# power.net
KiCad netlist of a schematic drawn in Altium Designer
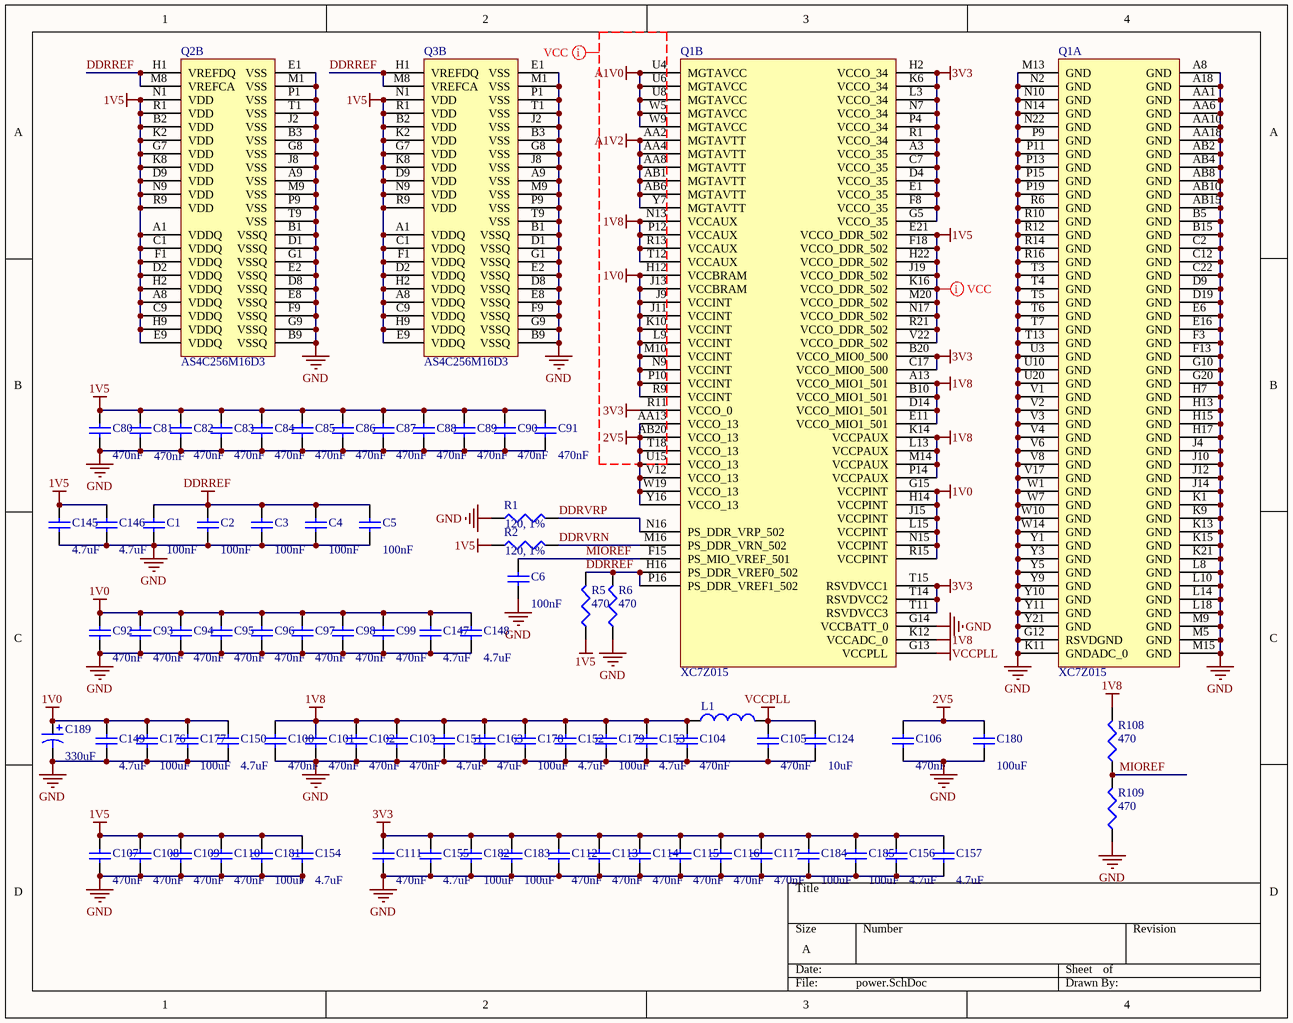
[diagram p0: power.SchDoc]

(export (version "E")
  (design (tool "Eeschema 10.0.6"))
  (components
    (comp (ref "C1")
      (value "100nF")
      (footprint "CAPC1005X06L")
      (description "Capacitor")
      (fields (field (name "Comment") "Cap") (field (name "PUBLISHER") "Altium Limited"))
      (libsource (lib "Miscellaneous Devices") (part "Cap"))
    )
    (comp (ref "C2")
      (value "100nF")
      (footprint "CAPC1005X06L")
      (description "Capacitor")
      (fields (field (name "Comment") "Cap") (field (name "PUBLISHER") "Altium Limited"))
      (libsource (lib "Miscellaneous Devices") (part "Cap"))
    )
    (comp (ref "C3")
      (value "100nF")
      (footprint "CAPC1005X06L")
      (description "Capacitor")
      (fields (field (name "Comment") "Cap") (field (name "PUBLISHER") "Altium Limited"))
      (libsource (lib "Miscellaneous Devices") (part "Cap"))
    )
    (comp (ref "C4")
      (value "100nF")
      (footprint "CAPC1005X06L")
      (description "Capacitor")
      (fields (field (name "Comment") "Cap") (field (name "PUBLISHER") "Altium Limited"))
      (libsource (lib "Miscellaneous Devices") (part "Cap"))
    )
    (comp (ref "C5")
      (value "100nF")
      (footprint "CAPC1005X06L")
      (description "Capacitor")
      (fields (field (name "Comment") "Cap") (field (name "PUBLISHER") "Altium Limited"))
      (libsource (lib "Miscellaneous Devices") (part "Cap"))
    )
    (comp (ref "C6")
      (value "100nF")
      (footprint "CAPC1005X06L")
      (description "Capacitor")
      (fields (field (name "Comment") "Cap") (field (name "PUBLISHER") "Altium Limited"))
      (libsource (lib "Miscellaneous Devices") (part "Cap"))
    )
    (comp (ref "C80")
      (value "470nF")
      (footprint "CAPC1005X06L")
      (description "Capacitor")
      (fields (field (name "Comment") "JMK105BJ474KV-F") (field (name "PUBLISHER") "Altium Limited"))
      (libsource (lib "Miscellaneous Devices") (part "Cap"))
    )
    (comp (ref "C81")
      (value "470nF")
      (footprint "CAPC1005X06L")
      (description "Capacitor")
      (fields (field (name "Comment") "JMK105BJ474KV-F") (field (name "PUBLISHER") "Altium Limited"))
      (libsource (lib "Miscellaneous Devices") (part "Cap"))
    )
    (comp (ref "C82")
      (value "470nF")
      (footprint "CAPC1005X06L")
      (description "Capacitor")
      (fields (field (name "Comment") "JMK105BJ474KV-F") (field (name "PUBLISHER") "Altium Limited"))
      (libsource (lib "Miscellaneous Devices") (part "Cap"))
    )
    (comp (ref "C83")
      (value "470nF")
      (footprint "CAPC1005X06L")
      (description "Capacitor")
      (fields (field (name "Comment") "JMK105BJ474KV-F") (field (name "PUBLISHER") "Altium Limited"))
      (libsource (lib "Miscellaneous Devices") (part "Cap"))
    )
    (comp (ref "C84")
      (value "470nF")
      (footprint "CAPC1005X06L")
      (description "Capacitor")
      (fields (field (name "Comment") "JMK105BJ474KV-F") (field (name "PUBLISHER") "Altium Limited"))
      (libsource (lib "Miscellaneous Devices") (part "Cap"))
    )
    (comp (ref "C85")
      (value "470nF")
      (footprint "CAPC1005X06L")
      (description "Capacitor")
      (fields (field (name "Comment") "JMK105BJ474KV-F") (field (name "PUBLISHER") "Altium Limited"))
      (libsource (lib "Miscellaneous Devices") (part "Cap"))
    )
    (comp (ref "C86")
      (value "470nF")
      (footprint "CAPC1005X06L")
      (description "Capacitor")
      (fields (field (name "Comment") "JMK105BJ474KV-F") (field (name "PUBLISHER") "Altium Limited"))
      (libsource (lib "Miscellaneous Devices") (part "Cap"))
    )
    (comp (ref "C87")
      (value "470nF")
      (footprint "CAPC1005X06L")
      (description "Capacitor")
      (fields (field (name "Comment") "JMK105BJ474KV-F") (field (name "PUBLISHER") "Altium Limited"))
      (libsource (lib "Miscellaneous Devices") (part "Cap"))
    )
    (comp (ref "C88")
      (value "470nF")
      (footprint "CAPC1005X06L")
      (description "Capacitor")
      (fields (field (name "Comment") "JMK105BJ474KV-F") (field (name "PUBLISHER") "Altium Limited"))
      (libsource (lib "Miscellaneous Devices") (part "Cap"))
    )
    (comp (ref "C89")
      (value "470nF")
      (footprint "CAPC1005X06L")
      (description "Capacitor")
      (fields (field (name "Comment") "JMK105BJ474KV-F") (field (name "PUBLISHER") "Altium Limited"))
      (libsource (lib "Miscellaneous Devices") (part "Cap"))
    )
    (comp (ref "C90")
      (value "470nF")
      (footprint "CAPC1005X06L")
      (description "Capacitor")
      (fields (field (name "Comment") "JMK105BJ474KV-F") (field (name "PUBLISHER") "Altium Limited"))
      (libsource (lib "Miscellaneous Devices") (part "Cap"))
    )
    (comp (ref "C91")
      (value "470nF")
      (footprint "CAPC1005X06L")
      (description "Capacitor")
      (fields (field (name "Comment") "JMK105BJ474KV-F") (field (name "PUBLISHER") "Altium Limited"))
      (libsource (lib "Miscellaneous Devices") (part "Cap"))
    )
    (comp (ref "C92")
      (value "470nF")
      (footprint "CAPC1005X06L")
      (description "Capacitor")
      (fields (field (name "Comment") "JMK105BJ474KV-F") (field (name "PUBLISHER") "Altium Limited"))
      (libsource (lib "Miscellaneous Devices") (part "Cap"))
    )
    (comp (ref "C93")
      (value "470nF")
      (footprint "CAPC1005X06L")
      (description "Capacitor")
      (fields (field (name "Comment") "JMK105BJ474KV-F") (field (name "PUBLISHER") "Altium Limited"))
      (libsource (lib "Miscellaneous Devices") (part "Cap"))
    )
    (comp (ref "C94")
      (value "470nF")
      (footprint "CAPC1005X06L")
      (description "Capacitor")
      (fields (field (name "Comment") "JMK105BJ474KV-F") (field (name "PUBLISHER") "Altium Limited"))
      (libsource (lib "Miscellaneous Devices") (part "Cap"))
    )
    (comp (ref "C95")
      (value "470nF")
      (footprint "CAPC1005X06L")
      (description "Capacitor")
      (fields (field (name "Comment") "JMK105BJ474KV-F") (field (name "PUBLISHER") "Altium Limited"))
      (libsource (lib "Miscellaneous Devices") (part "Cap"))
    )
    (comp (ref "C96")
      (value "470nF")
      (footprint "CAPC1005X06L")
      (description "Capacitor")
      (fields (field (name "Comment") "JMK105BJ474KV-F") (field (name "PUBLISHER") "Altium Limited"))
      (libsource (lib "Miscellaneous Devices") (part "Cap"))
    )
    (comp (ref "C97")
      (value "470nF")
      (footprint "CAPC1005X06L")
      (description "Capacitor")
      (fields (field (name "Comment") "JMK105BJ474KV-F") (field (name "PUBLISHER") "Altium Limited"))
      (libsource (lib "Miscellaneous Devices") (part "Cap"))
    )
    (comp (ref "C98")
      (value "470nF")
      (footprint "CAPC1005X06L")
      (description "Capacitor")
      (fields (field (name "Comment") "JMK105BJ474KV-F") (field (name "PUBLISHER") "Altium Limited"))
      (libsource (lib "Miscellaneous Devices") (part "Cap"))
    )
    (comp (ref "C99")
      (value "470nF")
      (footprint "CAPC1005X06L")
      (description "Capacitor")
      (fields (field (name "Comment") "JMK105BJ474KV-F") (field (name "PUBLISHER") "Altium Limited"))
      (libsource (lib "Miscellaneous Devices") (part "Cap"))
    )
    (comp (ref "C100")
      (value "470nF")
      (footprint "CAPC1005X06L")
      (description "Capacitor")
      (fields (field (name "Comment") "JMK105BJ474KV-F") (field (name "PUBLISHER") "Altium Limited"))
      (libsource (lib "Miscellaneous Devices") (part "Cap"))
    )
    (comp (ref "C101")
      (value "470nF")
      (footprint "CAPC1005X06L")
      (description "Capacitor")
      (fields (field (name "Comment") "JMK105BJ474KV-F") (field (name "PUBLISHER") "Altium Limited"))
      (libsource (lib "Miscellaneous Devices") (part "Cap"))
    )
    (comp (ref "C102")
      (value "470nF")
      (footprint "CAPC1005X06L")
      (description "Capacitor")
      (fields (field (name "Comment") "JMK105BJ474KV-F") (field (name "PUBLISHER") "Altium Limited"))
      (libsource (lib "Miscellaneous Devices") (part "Cap"))
    )
    (comp (ref "C103")
      (value "470nF")
      (footprint "CAPC1005X06L")
      (description "Capacitor")
      (fields (field (name "Comment") "JMK105BJ474KV-F") (field (name "PUBLISHER") "Altium Limited"))
      (libsource (lib "Miscellaneous Devices") (part "Cap"))
    )
    (comp (ref "C104")
      (value "470nF")
      (footprint "CAPC1005X06L")
      (description "Capacitor")
      (fields (field (name "Comment") "JMK105BJ474KV-F") (field (name "PUBLISHER") "Altium Limited"))
      (libsource (lib "Miscellaneous Devices") (part "Cap"))
    )
    (comp (ref "C105")
      (value "470nF")
      (footprint "CAPC1005X06L")
      (description "Capacitor")
      (fields (field (name "Comment") "JMK105BJ474KV-F") (field (name "PUBLISHER") "Altium Limited"))
      (libsource (lib "Miscellaneous Devices") (part "Cap"))
    )
    (comp (ref "C106")
      (value "470nF")
      (footprint "CAPC1005X06L")
      (description "Capacitor")
      (fields (field (name "Comment") "JMK105BJ474KV-F") (field (name "PUBLISHER") "Altium Limited"))
      (libsource (lib "Miscellaneous Devices") (part "Cap"))
    )
    (comp (ref "C107")
      (value "470nF")
      (footprint "CAPC1005X06L")
      (description "Capacitor")
      (fields (field (name "Comment") "JMK105BJ474KV-F") (field (name "PUBLISHER") "Altium Limited"))
      (libsource (lib "Miscellaneous Devices") (part "Cap"))
    )
    (comp (ref "C108")
      (value "470nF")
      (footprint "CAPC1005X06L")
      (description "Capacitor")
      (fields (field (name "Comment") "JMK105BJ474KV-F") (field (name "PUBLISHER") "Altium Limited"))
      (libsource (lib "Miscellaneous Devices") (part "Cap"))
    )
    (comp (ref "C109")
      (value "470nF")
      (footprint "CAPC1005X06L")
      (description "Capacitor")
      (fields (field (name "Comment") "JMK105BJ474KV-F") (field (name "PUBLISHER") "Altium Limited"))
      (libsource (lib "Miscellaneous Devices") (part "Cap"))
    )
    (comp (ref "C110")
      (value "470nF")
      (footprint "CAPC1005X06L")
      (description "Capacitor")
      (fields (field (name "Comment") "JMK105BJ474KV-F") (field (name "PUBLISHER") "Altium Limited"))
      (libsource (lib "Miscellaneous Devices") (part "Cap"))
    )
    (comp (ref "C111")
      (value "470nF")
      (footprint "CAPC1005X06L")
      (description "Capacitor")
      (fields (field (name "Comment") "JMK105BJ474KV-F") (field (name "PUBLISHER") "Altium Limited"))
      (libsource (lib "Miscellaneous Devices") (part "Cap"))
    )
    (comp (ref "C112")
      (value "470nF")
      (footprint "CAPC1005X06L")
      (description "Capacitor")
      (fields (field (name "Comment") "JMK105BJ474KV-F") (field (name "PUBLISHER") "Altium Limited"))
      (libsource (lib "Miscellaneous Devices") (part "Cap"))
    )
    (comp (ref "C113")
      (value "470nF")
      (footprint "CAPC1005X06L")
      (description "Capacitor")
      (fields (field (name "Comment") "JMK105BJ474KV-F") (field (name "PUBLISHER") "Altium Limited"))
      (libsource (lib "Miscellaneous Devices") (part "Cap"))
    )
    (comp (ref "C114")
      (value "470nF")
      (footprint "CAPC1005X06L")
      (description "Capacitor")
      (fields (field (name "Comment") "JMK105BJ474KV-F") (field (name "PUBLISHER") "Altium Limited"))
      (libsource (lib "Miscellaneous Devices") (part "Cap"))
    )
    (comp (ref "C115")
      (value "470nF")
      (footprint "CAPC1005X06L")
      (description "Capacitor")
      (fields (field (name "Comment") "JMK105BJ474KV-F") (field (name "PUBLISHER") "Altium Limited"))
      (libsource (lib "Miscellaneous Devices") (part "Cap"))
    )
    (comp (ref "C116")
      (value "470nF")
      (footprint "CAPC1005X06L")
      (description "Capacitor")
      (fields (field (name "Comment") "JMK105BJ474KV-F") (field (name "PUBLISHER") "Altium Limited"))
      (libsource (lib "Miscellaneous Devices") (part "Cap"))
    )
    (comp (ref "C117")
      (value "470nF")
      (footprint "CAPC1005X06L")
      (description "Capacitor")
      (fields (field (name "Comment") "JMK105BJ474KV-F") (field (name "PUBLISHER") "Altium Limited"))
      (libsource (lib "Miscellaneous Devices") (part "Cap"))
    )
    (comp (ref "C124")
      (value "10uF")
      (footprint "CAPC1608X90N")
      (description "Capacitor")
      (fields (field (name "Comment") "GRM188R60G106ME47") (field (name "PUBLISHER") "Altium Limited"))
      (libsource (lib "Miscellaneous Devices") (part "Cap"))
    )
    (comp (ref "C145")
      (value "4.7uF")
      (footprint "CAPC1608X90N")
      (description "Capacitor")
      (fields (field (name "Comment") "GRM188R60J475ME19D") (field (name "PUBLISHER") "Altium Limited"))
      (libsource (lib "Miscellaneous Devices") (part "Cap"))
    )
    (comp (ref "C146")
      (value "4.7uF")
      (footprint "CAPC1608X90N")
      (description "Capacitor")
      (fields (field (name "Comment") "GRM188R60J475ME19D") (field (name "PUBLISHER") "Altium Limited"))
      (libsource (lib "Miscellaneous Devices") (part "Cap"))
    )
    (comp (ref "C147")
      (value "4.7uF")
      (footprint "CAPC1608X90N")
      (description "Capacitor")
      (fields (field (name "Comment") "GRM188R60J475ME19D") (field (name "PUBLISHER") "Altium Limited"))
      (libsource (lib "Miscellaneous Devices") (part "Cap"))
    )
    (comp (ref "C148")
      (value "4.7uF")
      (footprint "CAPC1608X90N")
      (description "Capacitor")
      (fields (field (name "Comment") "GRM188R60J475ME19D") (field (name "PUBLISHER") "Altium Limited"))
      (libsource (lib "Miscellaneous Devices") (part "Cap"))
    )
    (comp (ref "C149")
      (value "4.7uF")
      (footprint "CAPC1608X90N")
      (description "Capacitor")
      (fields (field (name "Comment") "GRM188R60J475ME19D") (field (name "PUBLISHER") "Altium Limited"))
      (libsource (lib "Miscellaneous Devices") (part "Cap"))
    )
    (comp (ref "C150")
      (value "4.7uF")
      (footprint "CAPC1608X90N")
      (description "Capacitor")
      (fields (field (name "Comment") "GRM188R60J475ME19D") (field (name "PUBLISHER") "Altium Limited"))
      (libsource (lib "Miscellaneous Devices") (part "Cap"))
    )
    (comp (ref "C151")
      (value "4.7uF")
      (footprint "CAPC1608X90N")
      (description "Capacitor")
      (fields (field (name "Comment") "GRM188R60J475ME19D") (field (name "PUBLISHER") "Altium Limited"))
      (libsource (lib "Miscellaneous Devices") (part "Cap"))
    )
    (comp (ref "C152")
      (value "4.7uF")
      (footprint "CAPC1608X90N")
      (description "Capacitor")
      (fields (field (name "Comment") "GRM188R60J475ME19D") (field (name "PUBLISHER") "Altium Limited"))
      (libsource (lib "Miscellaneous Devices") (part "Cap"))
    )
    (comp (ref "C153")
      (value "4.7uF")
      (footprint "CAPC1608X90N")
      (description "Capacitor")
      (fields (field (name "Comment") "GRM188R60J475ME19D") (field (name "PUBLISHER") "Altium Limited"))
      (libsource (lib "Miscellaneous Devices") (part "Cap"))
    )
    (comp (ref "C154")
      (value "4.7uF")
      (footprint "CAPC1608X90N")
      (description "Capacitor")
      (fields (field (name "Comment") "GRM188R60J475ME19D") (field (name "PUBLISHER") "Altium Limited"))
      (libsource (lib "Miscellaneous Devices") (part "Cap"))
    )
    (comp (ref "C155")
      (value "4.7uF")
      (footprint "CAPC1608X90N")
      (description "Capacitor")
      (fields (field (name "Comment") "GRM188R60J475ME19D") (field (name "PUBLISHER") "Altium Limited"))
      (libsource (lib "Miscellaneous Devices") (part "Cap"))
    )
    (comp (ref "C156")
      (value "4.7uF")
      (footprint "CAPC1608X90N")
      (description "Capacitor")
      (fields (field (name "Comment") "GRM188R60J475ME19D") (field (name "PUBLISHER") "Altium Limited"))
      (libsource (lib "Miscellaneous Devices") (part "Cap"))
    )
    (comp (ref "C157")
      (value "4.7uF")
      (footprint "CAPC1608X90N")
      (description "Capacitor")
      (fields (field (name "Comment") "GRM188R60J475ME19D") (field (name "PUBLISHER") "Altium Limited"))
      (libsource (lib "Miscellaneous Devices") (part "Cap"))
    )
    (comp (ref "C163")
      (value "47uF")
      (footprint "CAPC3225X220N")
      (description "Capacitor")
      (fields (field (name "Comment") "GRM31CR60J476ME19L") (field (name "PUBLISHER") "Altium Limited"))
      (libsource (lib "Miscellaneous Devices") (part "Cap"))
    )
    (comp (ref "C176")
      (value "100uF")
      (footprint "CAPC3225X220N")
      (description "Capacitor")
      (fields (field (name "Comment") "GRM31CR60J107ME39L") (field (name "PUBLISHER") "Altium Limited"))
      (libsource (lib "Miscellaneous Devices") (part "Cap"))
    )
    (comp (ref "C177")
      (value "100uF")
      (footprint "CAPC3225X220N")
      (description "Capacitor")
      (fields (field (name "Comment") "GRM31CR60J107ME39L") (field (name "PUBLISHER") "Altium Limited"))
      (libsource (lib "Miscellaneous Devices") (part "Cap"))
    )
    (comp (ref "C178")
      (value "100uF")
      (footprint "CAPC3225X220N")
      (description "Capacitor")
      (fields (field (name "Comment") "GRM31CR60J107ME39L") (field (name "PUBLISHER") "Altium Limited"))
      (libsource (lib "Miscellaneous Devices") (part "Cap"))
    )
    (comp (ref "C179")
      (value "100uF")
      (footprint "CAPC3225X220N")
      (description "Capacitor")
      (fields (field (name "Comment") "GRM31CR60J107ME39L") (field (name "PUBLISHER") "Altium Limited"))
      (libsource (lib "Miscellaneous Devices") (part "Cap"))
    )
    (comp (ref "C180")
      (value "100uF")
      (footprint "CAPC3225X220N")
      (description "Capacitor")
      (fields (field (name "Comment") "GRM31CR60J107ME39L") (field (name "PUBLISHER") "Altium Limited"))
      (libsource (lib "Miscellaneous Devices") (part "Cap"))
    )
    (comp (ref "C181")
      (value "100uF")
      (footprint "CAPC3225X220N")
      (description "Capacitor")
      (fields (field (name "Comment") "GRM31CR60J107ME39L") (field (name "PUBLISHER") "Altium Limited"))
      (libsource (lib "Miscellaneous Devices") (part "Cap"))
    )
    (comp (ref "C182")
      (value "100uF")
      (footprint "CAPC3225X220N")
      (description "Capacitor")
      (fields (field (name "Comment") "GRM31CR60J107ME39L") (field (name "PUBLISHER") "Altium Limited"))
      (libsource (lib "Miscellaneous Devices") (part "Cap"))
    )
    (comp (ref "C183")
      (value "100uF")
      (footprint "CAPC3225X220N")
      (description "Capacitor")
      (fields (field (name "Comment") "GRM31CR60J107ME39L") (field (name "PUBLISHER") "Altium Limited"))
      (libsource (lib "Miscellaneous Devices") (part "Cap"))
    )
    (comp (ref "C184")
      (value "100uF")
      (footprint "CAPC3225X220N")
      (description "Capacitor")
      (fields (field (name "Comment") "GRM31CR60J107ME39L") (field (name "PUBLISHER") "Altium Limited"))
      (libsource (lib "Miscellaneous Devices") (part "Cap"))
    )
    (comp (ref "C185")
      (value "100uF")
      (footprint "CAPC3225X220N")
      (description "Capacitor")
      (fields (field (name "Comment") "GRM31CR60J107ME39L") (field (name "PUBLISHER") "Altium Limited"))
      (libsource (lib "Miscellaneous Devices") (part "Cap"))
    )
    (comp (ref "C189")
      (value "330uF")
      (footprint "CAP-D/7343-31")
      (description "Polarized Capacitor (Radial)")
      (fields (field (name "Comment") "T520D337M006ATE018") (field (name "PUBLISHER") "Altium Limited"))
      (libsource (lib "Miscellaneous Devices") (part "Cap Pol1"))
    )
    (comp (ref "L1")
      (value "BLM18SG121TN1")
      (footprint "CAPC1608X90N")
      (description "Inductor")
      (fields (field (name "PUBLISHER") "Altium Limited"))
      (libsource (lib "Miscellaneous Devices") (part "Inductor"))
    )
    (comp (ref "Q1") (value "XC7Z015") (footprint "BGA484x22") (libsource (lib "schlib") (part "XC7Z015")))
    (comp (ref "Q2")
      (value "AS4C256M16D3")
      (footprint "DDR3")
      (libsource (lib "schlib") (part "AS4C256M16D3"))
    )
    (comp (ref "Q3")
      (value "AS4C256M16D3")
      (footprint "DDR3")
      (libsource (lib "schlib") (part "AS4C256M16D3"))
    )
    (comp (ref "R1")
      (value "120, 1%")
      (footprint "CAPC1005X06L")
      (description "Resistor")
      (fields (field (name "Comment") "RC1005F121CS") (field (name "PUBLISHER") "Altium Limited"))
      (libsource (lib "Miscellaneous Devices") (part "Res3"))
    )
    (comp (ref "R2")
      (value "120, 1%")
      (footprint "CAPC1005X06L")
      (description "Resistor")
      (fields (field (name "Comment") "RC1005F121CS") (field (name "PUBLISHER") "Altium Limited"))
      (libsource (lib "Miscellaneous Devices") (part "Res3"))
    )
    (comp (ref "R5")
      (value "470")
      (footprint "J1-0603")
      (description "Resistor")
      (fields (field (name "Comment") "RC1608F471CS") (field (name "PUBLISHER") "Altium Limited"))
      (libsource (lib "Miscellaneous Devices") (part "Res3"))
    )
    (comp (ref "R6")
      (value "470")
      (footprint "J1-0603")
      (description "Resistor")
      (fields (field (name "Comment") "RC1608F471CS") (field (name "PUBLISHER") "Altium Limited"))
      (libsource (lib "Miscellaneous Devices") (part "Res3"))
    )
    (comp (ref "R108")
      (value "470")
      (footprint "CAPC1005X06L")
      (description "Resistor")
      (fields (field (name "Comment") "RC1005F471CS") (field (name "PUBLISHER") "Altium Limited"))
      (libsource (lib "Miscellaneous Devices") (part "Res3"))
    )
    (comp (ref "R109")
      (value "470")
      (footprint "CAPC1005X06L")
      (description "Resistor")
      (fields (field (name "Comment") "RC1005F471CS") (field (name "PUBLISHER") "Altium Limited"))
      (libsource (lib "Miscellaneous Devices") (part "Res3"))
    )
  )
  (nets
    (net (code "1") (name "/DDRVRN") (class "Default")
      (node (ref "Q1") (pin "M16") (pinfunction "PS_DDR_VRN_502_M16") (pintype "passive"))
      (node (ref "R2") (pin "2") (pinfunction "2_2") (pintype "passive"))
    )
    (net (code "2") (name "/DDRVRP") (class "Default")
      (node (ref "Q1") (pin "N16") (pinfunction "PS_DDR_VRP_502_N16") (pintype "passive"))
      (node (ref "R1") (pin "2") (pinfunction "2_2") (pintype "passive"))
    )
    (net (code "3") (name "/MIOREF") (class "Default")
      (node (ref "C6") (pin "2") (pinfunction "2_2") (pintype "passive"))
      (node (ref "Q1") (pin "F15") (pinfunction "PS_MIO_VREF_501_F15") (pintype "passive"))
      (node (ref "R108") (pin "1") (pinfunction "1_1") (pintype "passive"))
      (node (ref "R109") (pin "2") (pinfunction "2_2") (pintype "passive"))
    )
    (net (code "4") (name "1V0") (class "Default")
      (node (ref "C147") (pin "2") (pinfunction "2_2") (pintype "passive"))
      (node (ref "C148") (pin "2") (pinfunction "2_2") (pintype "passive"))
      (node (ref "C149") (pin "2") (pinfunction "2_2") (pintype "passive"))
      (node (ref "C150") (pin "2") (pinfunction "2_2") (pintype "passive"))
      (node (ref "C176") (pin "2") (pinfunction "2_2") (pintype "passive"))
      (node (ref "C177") (pin "2") (pinfunction "2_2") (pintype "passive"))
      (node (ref "C189") (pin "1") (pinfunction "1_1") (pintype "passive"))
      (node (ref "C92") (pin "2") (pinfunction "2_2") (pintype "passive"))
      (node (ref "C93") (pin "2") (pinfunction "2_2") (pintype "passive"))
      (node (ref "C94") (pin "2") (pinfunction "2_2") (pintype "passive"))
      (node (ref "C95") (pin "2") (pinfunction "2_2") (pintype "passive"))
      (node (ref "C96") (pin "2") (pinfunction "2_2") (pintype "passive"))
      (node (ref "C97") (pin "2") (pinfunction "2_2") (pintype "passive"))
      (node (ref "C98") (pin "2") (pinfunction "2_2") (pintype "passive"))
      (node (ref "C99") (pin "2") (pinfunction "2_2") (pintype "passive"))
      (node (ref "Q1") (pin "G15") (pinfunction "VCCPINT_G15") (pintype "passive"))
      (node (ref "Q1") (pin "H12") (pinfunction "VCCBRAM_H12") (pintype "passive"))
      (node (ref "Q1") (pin "H14") (pinfunction "VCCPINT_H14") (pintype "passive"))
      (node (ref "Q1") (pin "J11") (pinfunction "VCCINT_J11") (pintype "passive"))
      (node (ref "Q1") (pin "J13") (pinfunction "VCCBRAM_J13") (pintype "passive"))
      (node (ref "Q1") (pin "J15") (pinfunction "VCCPINT_J15") (pintype "passive"))
      (node (ref "Q1") (pin "J9") (pinfunction "VCCINT_J9") (pintype "passive"))
      (node (ref "Q1") (pin "K10") (pinfunction "VCCINT_K10") (pintype "passive"))
      (node (ref "Q1") (pin "L15") (pinfunction "VCCPINT_L15") (pintype "passive"))
      (node (ref "Q1") (pin "L9") (pinfunction "VCCINT_L9") (pintype "passive"))
      (node (ref "Q1") (pin "M10") (pinfunction "VCCINT_M10") (pintype "passive"))
      (node (ref "Q1") (pin "N15") (pinfunction "VCCPINT_N15") (pintype "passive"))
      (node (ref "Q1") (pin "N9") (pinfunction "VCCINT_N9") (pintype "passive"))
      (node (ref "Q1") (pin "P10") (pinfunction "VCCINT_P10") (pintype "passive"))
      (node (ref "Q1") (pin "R15") (pinfunction "VCCPINT_R15") (pintype "passive"))
      (node (ref "Q1") (pin "R9") (pinfunction "VCCINT_R9") (pintype "passive"))
    )
    (net (code "5") (name "1V5") (class "Default")
      (node (ref "C107") (pin "2") (pinfunction "2_2") (pintype "passive"))
      (node (ref "C108") (pin "2") (pinfunction "2_2") (pintype "passive"))
      (node (ref "C109") (pin "2") (pinfunction "2_2") (pintype "passive"))
      (node (ref "C110") (pin "2") (pinfunction "2_2") (pintype "passive"))
      (node (ref "C145") (pin "2") (pinfunction "2_2") (pintype "passive"))
      (node (ref "C146") (pin "2") (pinfunction "2_2") (pintype "passive"))
      (node (ref "C154") (pin "2") (pinfunction "2_2") (pintype "passive"))
      (node (ref "C181") (pin "2") (pinfunction "2_2") (pintype "passive"))
      (node (ref "C80") (pin "2") (pinfunction "2_2") (pintype "passive"))
      (node (ref "C81") (pin "2") (pinfunction "2_2") (pintype "passive"))
      (node (ref "C82") (pin "2") (pinfunction "2_2") (pintype "passive"))
      (node (ref "C83") (pin "2") (pinfunction "2_2") (pintype "passive"))
      (node (ref "C84") (pin "2") (pinfunction "2_2") (pintype "passive"))
      (node (ref "C85") (pin "2") (pinfunction "2_2") (pintype "passive"))
      (node (ref "C86") (pin "2") (pinfunction "2_2") (pintype "passive"))
      (node (ref "C87") (pin "2") (pinfunction "2_2") (pintype "passive"))
      (node (ref "C88") (pin "2") (pinfunction "2_2") (pintype "passive"))
      (node (ref "C89") (pin "2") (pinfunction "2_2") (pintype "passive"))
      (node (ref "C90") (pin "2") (pinfunction "2_2") (pintype "passive"))
      (node (ref "C91") (pin "2") (pinfunction "2_2") (pintype "passive"))
      (node (ref "Q1") (pin "E21") (pinfunction "VCCO_DDR_502_E21") (pintype "passive"))
      (node (ref "Q1") (pin "F18") (pinfunction "VCCO_DDR_502_F18") (pintype "passive"))
      (node (ref "Q1") (pin "H22") (pinfunction "VCCO_DDR_502_H22") (pintype "passive"))
      (node (ref "Q1") (pin "J19") (pinfunction "VCCO_DDR_502_J19") (pintype "passive"))
      (node (ref "Q1") (pin "K16") (pinfunction "VCCO_DDR_502_K16") (pintype "passive"))
      (node (ref "Q1") (pin "M20") (pinfunction "VCCO_DDR_502_M20") (pintype "passive"))
      (node (ref "Q1") (pin "N17") (pinfunction "VCCO_DDR_502_N17") (pintype "passive"))
      (node (ref "Q1") (pin "R21") (pinfunction "VCCO_DDR_502_R21") (pintype "passive"))
      (node (ref "Q1") (pin "V22") (pinfunction "VCCO_DDR_502_V22") (pintype "passive"))
      (node (ref "Q2") (pin "A1") (pinfunction "VDDQ_A1") (pintype "passive"))
      (node (ref "Q2") (pin "A8") (pinfunction "VDDQ_A8") (pintype "passive"))
      (node (ref "Q2") (pin "B2") (pinfunction "VDD_B2") (pintype "passive"))
      (node (ref "Q2") (pin "C1") (pinfunction "VDDQ_C1") (pintype "passive"))
      (node (ref "Q2") (pin "C9") (pinfunction "VDDQ_C9") (pintype "passive"))
      (node (ref "Q2") (pin "D2") (pinfunction "VDDQ_D2") (pintype "passive"))
      (node (ref "Q2") (pin "D9") (pinfunction "VDD_D9") (pintype "passive"))
      (node (ref "Q2") (pin "E9") (pinfunction "VDDQ_E9") (pintype "passive"))
      (node (ref "Q2") (pin "F1") (pinfunction "VDDQ_F1") (pintype "passive"))
      (node (ref "Q2") (pin "G7") (pinfunction "VDD_G7") (pintype "passive"))
      (node (ref "Q2") (pin "H2") (pinfunction "VDDQ_H2") (pintype "passive"))
      (node (ref "Q2") (pin "H9") (pinfunction "VDDQ_H9") (pintype "passive"))
      (node (ref "Q2") (pin "K2") (pinfunction "VDD_K2") (pintype "passive"))
      (node (ref "Q2") (pin "K8") (pinfunction "VDD_K8") (pintype "passive"))
      (node (ref "Q2") (pin "N1") (pinfunction "VDD_N1") (pintype "passive"))
      (node (ref "Q2") (pin "N9") (pinfunction "VDD_N9") (pintype "passive"))
      (node (ref "Q2") (pin "R1") (pinfunction "VDD_R1") (pintype "passive"))
      (node (ref "Q2") (pin "R9") (pinfunction "VDD_R9") (pintype "passive"))
      (node (ref "Q3") (pin "A1") (pinfunction "VDDQ_A1") (pintype "passive"))
      (node (ref "Q3") (pin "A8") (pinfunction "VDDQ_A8") (pintype "passive"))
      (node (ref "Q3") (pin "B2") (pinfunction "VDD_B2") (pintype "passive"))
      (node (ref "Q3") (pin "C1") (pinfunction "VDDQ_C1") (pintype "passive"))
      (node (ref "Q3") (pin "C9") (pinfunction "VDDQ_C9") (pintype "passive"))
      (node (ref "Q3") (pin "D2") (pinfunction "VDDQ_D2") (pintype "passive"))
      (node (ref "Q3") (pin "D9") (pinfunction "VDD_D9") (pintype "passive"))
      (node (ref "Q3") (pin "E9") (pinfunction "VDDQ_E9") (pintype "passive"))
      (node (ref "Q3") (pin "F1") (pinfunction "VDDQ_F1") (pintype "passive"))
      (node (ref "Q3") (pin "G7") (pinfunction "VDD_G7") (pintype "passive"))
      (node (ref "Q3") (pin "H2") (pinfunction "VDDQ_H2") (pintype "passive"))
      (node (ref "Q3") (pin "H9") (pinfunction "VDDQ_H9") (pintype "passive"))
      (node (ref "Q3") (pin "K2") (pinfunction "VDD_K2") (pintype "passive"))
      (node (ref "Q3") (pin "K8") (pinfunction "VDD_K8") (pintype "passive"))
      (node (ref "Q3") (pin "N1") (pinfunction "VDD_N1") (pintype "passive"))
      (node (ref "Q3") (pin "N9") (pinfunction "VDD_N9") (pintype "passive"))
      (node (ref "Q3") (pin "R1") (pinfunction "VDD_R1") (pintype "passive"))
      (node (ref "Q3") (pin "R9") (pinfunction "VDD_R9") (pintype "passive"))
      (node (ref "R2") (pin "1") (pinfunction "1_1") (pintype "passive"))
      (node (ref "R5") (pin "1") (pinfunction "1_1") (pintype "passive"))
    )
    (net (code "6") (name "1V8") (class "Default")
      (node (ref "C100") (pin "2") (pinfunction "2_2") (pintype "passive"))
      (node (ref "C101") (pin "2") (pinfunction "2_2") (pintype "passive"))
      (node (ref "C102") (pin "2") (pinfunction "2_2") (pintype "passive"))
      (node (ref "C103") (pin "2") (pinfunction "2_2") (pintype "passive"))
      (node (ref "C104") (pin "2") (pinfunction "2_2") (pintype "passive"))
      (node (ref "C151") (pin "2") (pinfunction "2_2") (pintype "passive"))
      (node (ref "C152") (pin "2") (pinfunction "2_2") (pintype "passive"))
      (node (ref "C153") (pin "2") (pinfunction "2_2") (pintype "passive"))
      (node (ref "C163") (pin "2") (pinfunction "2_2") (pintype "passive"))
      (node (ref "C178") (pin "2") (pinfunction "2_2") (pintype "passive"))
      (node (ref "C179") (pin "2") (pinfunction "2_2") (pintype "passive"))
      (node (ref "L1") (pin "1") (pinfunction "1_1") (pintype "passive"))
      (node (ref "Q1") (pin "A13") (pinfunction "VCCO_MIO1_501_A13") (pintype "passive"))
      (node (ref "Q1") (pin "B10") (pinfunction "VCCO_MIO1_501_B10") (pintype "passive"))
      (node (ref "Q1") (pin "D14") (pinfunction "VCCO_MIO1_501_D14") (pintype "passive"))
      (node (ref "Q1") (pin "E11") (pinfunction "VCCO_MIO1_501_E11") (pintype "passive"))
      (node (ref "Q1") (pin "K12") (pinfunction "VCCADC_0_K12") (pintype "passive"))
      (node (ref "Q1") (pin "K14") (pinfunction "VCCPAUX_K14") (pintype "passive"))
      (node (ref "Q1") (pin "L13") (pinfunction "VCCPAUX_L13") (pintype "passive"))
      (node (ref "Q1") (pin "M14") (pinfunction "VCCPAUX_M14") (pintype "passive"))
      (node (ref "Q1") (pin "N13") (pinfunction "VCCAUX_N13") (pintype "passive"))
      (node (ref "Q1") (pin "P12") (pinfunction "VCCAUX_P12") (pintype "passive"))
      (node (ref "Q1") (pin "P14") (pinfunction "VCCPAUX_P14") (pintype "passive"))
      (node (ref "Q1") (pin "R13") (pinfunction "VCCAUX_R13") (pintype "passive"))
      (node (ref "Q1") (pin "T12") (pinfunction "VCCAUX_T12") (pintype "passive"))
      (node (ref "R108") (pin "2") (pinfunction "2_2") (pintype "passive"))
    )
    (net (code "7") (name "2V5") (class "Default")
      (node (ref "C106") (pin "2") (pinfunction "2_2") (pintype "passive"))
      (node (ref "C180") (pin "2") (pinfunction "2_2") (pintype "passive"))
      (node (ref "Q1") (pin "AA13") (pinfunction "VCCO_13_AA13") (pintype "passive"))
      (node (ref "Q1") (pin "AB20") (pinfunction "VCCO_13_AB20") (pintype "passive"))
      (node (ref "Q1") (pin "T18") (pinfunction "VCCO_13_T18") (pintype "passive"))
      (node (ref "Q1") (pin "U15") (pinfunction "VCCO_13_U15") (pintype "passive"))
      (node (ref "Q1") (pin "V12") (pinfunction "VCCO_13_V12") (pintype "passive"))
      (node (ref "Q1") (pin "W19") (pinfunction "VCCO_13_W19") (pintype "passive"))
      (node (ref "Q1") (pin "Y16") (pinfunction "VCCO_13_Y16") (pintype "passive"))
    )
    (net (code "8") (name "3V3") (class "Default")
      (node (ref "C111") (pin "2") (pinfunction "2_2") (pintype "passive"))
      (node (ref "C112") (pin "2") (pinfunction "2_2") (pintype "passive"))
      (node (ref "C113") (pin "2") (pinfunction "2_2") (pintype "passive"))
      (node (ref "C114") (pin "2") (pinfunction "2_2") (pintype "passive"))
      (node (ref "C115") (pin "2") (pinfunction "2_2") (pintype "passive"))
      (node (ref "C116") (pin "2") (pinfunction "2_2") (pintype "passive"))
      (node (ref "C117") (pin "2") (pinfunction "2_2") (pintype "passive"))
      (node (ref "C155") (pin "2") (pinfunction "2_2") (pintype "passive"))
      (node (ref "C156") (pin "2") (pinfunction "2_2") (pintype "passive"))
      (node (ref "C157") (pin "2") (pinfunction "2_2") (pintype "passive"))
      (node (ref "C182") (pin "2") (pinfunction "2_2") (pintype "passive"))
      (node (ref "C183") (pin "2") (pinfunction "2_2") (pintype "passive"))
      (node (ref "C184") (pin "2") (pinfunction "2_2") (pintype "passive"))
      (node (ref "C185") (pin "2") (pinfunction "2_2") (pintype "passive"))
      (node (ref "Q1") (pin "A3") (pinfunction "VCCO_35_A3") (pintype "passive"))
      (node (ref "Q1") (pin "B20") (pinfunction "VCCO_MIO0_500_B20") (pintype "passive"))
      (node (ref "Q1") (pin "C17") (pinfunction "VCCO_MIO0_500_C17") (pintype "passive"))
      (node (ref "Q1") (pin "C7") (pinfunction "VCCO_35_C7") (pintype "passive"))
      (node (ref "Q1") (pin "D4") (pinfunction "VCCO_35_D4") (pintype "passive"))
      (node (ref "Q1") (pin "E1") (pinfunction "VCCO_35_E1") (pintype "passive"))
      (node (ref "Q1") (pin "F8") (pinfunction "VCCO_35_F8") (pintype "passive"))
      (node (ref "Q1") (pin "G5") (pinfunction "VCCO_35_G5") (pintype "passive"))
      (node (ref "Q1") (pin "H2") (pinfunction "VCCO_34_H2") (pintype "passive"))
      (node (ref "Q1") (pin "K6") (pinfunction "VCCO_34_K6") (pintype "passive"))
      (node (ref "Q1") (pin "L3") (pinfunction "VCCO_34_L3") (pintype "passive"))
      (node (ref "Q1") (pin "N7") (pinfunction "VCCO_34_N7") (pintype "passive"))
      (node (ref "Q1") (pin "P4") (pinfunction "VCCO_34_P4") (pintype "passive"))
      (node (ref "Q1") (pin "R1") (pinfunction "VCCO_34_R1") (pintype "passive"))
      (node (ref "Q1") (pin "R11") (pinfunction "VCCO_0_R11") (pintype "passive"))
      (node (ref "Q1") (pin "T11") (pinfunction "RSVDVCC3_T11") (pintype "passive"))
      (node (ref "Q1") (pin "T14") (pinfunction "RSVDVCC2_T14") (pintype "passive"))
      (node (ref "Q1") (pin "T15") (pinfunction "RSVDVCC1_T15") (pintype "passive"))
    )
    (net (code "9") (name "A1V0") (class "Default")
      (node (ref "Q1") (pin "U4") (pinfunction "MGTAVCC_U4") (pintype "passive"))
      (node (ref "Q1") (pin "U6") (pinfunction "MGTAVCC_U6") (pintype "passive"))
      (node (ref "Q1") (pin "U8") (pinfunction "MGTAVCC_U8") (pintype "passive"))
      (node (ref "Q1") (pin "W5") (pinfunction "MGTAVCC_W5") (pintype "passive"))
      (node (ref "Q1") (pin "W9") (pinfunction "MGTAVCC_W9") (pintype "passive"))
    )
    (net (code "10") (name "A1V2") (class "Default")
      (node (ref "Q1") (pin "AA2") (pinfunction "MGTAVTT_AA2") (pintype "passive"))
      (node (ref "Q1") (pin "AA4") (pinfunction "MGTAVTT_AA4") (pintype "passive"))
      (node (ref "Q1") (pin "AA8") (pinfunction "MGTAVTT_AA8") (pintype "passive"))
      (node (ref "Q1") (pin "AB1") (pinfunction "MGTAVTT_AB1") (pintype "passive"))
      (node (ref "Q1") (pin "AB6") (pinfunction "MGTAVTT_AB6") (pintype "passive"))
      (node (ref "Q1") (pin "Y7") (pinfunction "MGTAVTT_Y7") (pintype "passive"))
    )
    (net (code "11") (name "DDRREF") (class "Default")
      (node (ref "C1") (pin "2") (pinfunction "2_2") (pintype "passive"))
      (node (ref "C2") (pin "2") (pinfunction "2_2") (pintype "passive"))
      (node (ref "C3") (pin "2") (pinfunction "2_2") (pintype "passive"))
      (node (ref "C4") (pin "2") (pinfunction "2_2") (pintype "passive"))
      (node (ref "C5") (pin "2") (pinfunction "2_2") (pintype "passive"))
      (node (ref "Q1") (pin "H16") (pinfunction "PS_DDR_VREF0_502_H16") (pintype "passive"))
      (node (ref "Q1") (pin "P16") (pinfunction "PS_DDR_VREF1_502_P16") (pintype "passive"))
      (node (ref "Q2") (pin "H1") (pinfunction "VREFDQ_H1") (pintype "passive"))
      (node (ref "Q2") (pin "M8") (pinfunction "VREFCA_M8") (pintype "passive"))
      (node (ref "Q3") (pin "H1") (pinfunction "VREFDQ_H1") (pintype "passive"))
      (node (ref "Q3") (pin "M8") (pinfunction "VREFCA_M8") (pintype "passive"))
      (node (ref "R5") (pin "2") (pinfunction "2_2") (pintype "passive"))
      (node (ref "R6") (pin "2") (pinfunction "2_2") (pintype "passive"))
    )
    (net (code "12") (name "GND") (class "Default")
      (node (ref "C1") (pin "1") (pinfunction "1_1") (pintype "passive"))
      (node (ref "C100") (pin "1") (pinfunction "1_1") (pintype "passive"))
      (node (ref "C101") (pin "1") (pinfunction "1_1") (pintype "passive"))
      (node (ref "C102") (pin "1") (pinfunction "1_1") (pintype "passive"))
      (node (ref "C103") (pin "1") (pinfunction "1_1") (pintype "passive"))
      (node (ref "C104") (pin "1") (pinfunction "1_1") (pintype "passive"))
      (node (ref "C105") (pin "1") (pinfunction "1_1") (pintype "passive"))
      (node (ref "C106") (pin "1") (pinfunction "1_1") (pintype "passive"))
      (node (ref "C107") (pin "1") (pinfunction "1_1") (pintype "passive"))
      (node (ref "C108") (pin "1") (pinfunction "1_1") (pintype "passive"))
      (node (ref "C109") (pin "1") (pinfunction "1_1") (pintype "passive"))
      (node (ref "C110") (pin "1") (pinfunction "1_1") (pintype "passive"))
      (node (ref "C111") (pin "1") (pinfunction "1_1") (pintype "passive"))
      (node (ref "C112") (pin "1") (pinfunction "1_1") (pintype "passive"))
      (node (ref "C113") (pin "1") (pinfunction "1_1") (pintype "passive"))
      (node (ref "C114") (pin "1") (pinfunction "1_1") (pintype "passive"))
      (node (ref "C115") (pin "1") (pinfunction "1_1") (pintype "passive"))
      (node (ref "C116") (pin "1") (pinfunction "1_1") (pintype "passive"))
      (node (ref "C117") (pin "1") (pinfunction "1_1") (pintype "passive"))
      (node (ref "C124") (pin "1") (pinfunction "1_1") (pintype "passive"))
      (node (ref "C145") (pin "1") (pinfunction "1_1") (pintype "passive"))
      (node (ref "C146") (pin "1") (pinfunction "1_1") (pintype "passive"))
      (node (ref "C147") (pin "1") (pinfunction "1_1") (pintype "passive"))
      (node (ref "C148") (pin "1") (pinfunction "1_1") (pintype "passive"))
      (node (ref "C149") (pin "1") (pinfunction "1_1") (pintype "passive"))
      (node (ref "C150") (pin "1") (pinfunction "1_1") (pintype "passive"))
      (node (ref "C151") (pin "1") (pinfunction "1_1") (pintype "passive"))
      (node (ref "C152") (pin "1") (pinfunction "1_1") (pintype "passive"))
      (node (ref "C153") (pin "1") (pinfunction "1_1") (pintype "passive"))
      (node (ref "C154") (pin "1") (pinfunction "1_1") (pintype "passive"))
      (node (ref "C155") (pin "1") (pinfunction "1_1") (pintype "passive"))
      (node (ref "C156") (pin "1") (pinfunction "1_1") (pintype "passive"))
      (node (ref "C157") (pin "1") (pinfunction "1_1") (pintype "passive"))
      (node (ref "C163") (pin "1") (pinfunction "1_1") (pintype "passive"))
      (node (ref "C176") (pin "1") (pinfunction "1_1") (pintype "passive"))
      (node (ref "C177") (pin "1") (pinfunction "1_1") (pintype "passive"))
      (node (ref "C178") (pin "1") (pinfunction "1_1") (pintype "passive"))
      (node (ref "C179") (pin "1") (pinfunction "1_1") (pintype "passive"))
      (node (ref "C180") (pin "1") (pinfunction "1_1") (pintype "passive"))
      (node (ref "C181") (pin "1") (pinfunction "1_1") (pintype "passive"))
      (node (ref "C182") (pin "1") (pinfunction "1_1") (pintype "passive"))
      (node (ref "C183") (pin "1") (pinfunction "1_1") (pintype "passive"))
      (node (ref "C184") (pin "1") (pinfunction "1_1") (pintype "passive"))
      (node (ref "C185") (pin "1") (pinfunction "1_1") (pintype "passive"))
      (node (ref "C189") (pin "2") (pinfunction "2_2") (pintype "passive"))
      (node (ref "C2") (pin "1") (pinfunction "1_1") (pintype "passive"))
      (node (ref "C3") (pin "1") (pinfunction "1_1") (pintype "passive"))
      (node (ref "C4") (pin "1") (pinfunction "1_1") (pintype "passive"))
      (node (ref "C5") (pin "1") (pinfunction "1_1") (pintype "passive"))
      (node (ref "C6") (pin "1") (pinfunction "1_1") (pintype "passive"))
      (node (ref "C80") (pin "1") (pinfunction "1_1") (pintype "passive"))
      (node (ref "C81") (pin "1") (pinfunction "1_1") (pintype "passive"))
      (node (ref "C82") (pin "1") (pinfunction "1_1") (pintype "passive"))
      (node (ref "C83") (pin "1") (pinfunction "1_1") (pintype "passive"))
      (node (ref "C84") (pin "1") (pinfunction "1_1") (pintype "passive"))
      (node (ref "C85") (pin "1") (pinfunction "1_1") (pintype "passive"))
      (node (ref "C86") (pin "1") (pinfunction "1_1") (pintype "passive"))
      (node (ref "C87") (pin "1") (pinfunction "1_1") (pintype "passive"))
      (node (ref "C88") (pin "1") (pinfunction "1_1") (pintype "passive"))
      (node (ref "C89") (pin "1") (pinfunction "1_1") (pintype "passive"))
      (node (ref "C90") (pin "1") (pinfunction "1_1") (pintype "passive"))
      (node (ref "C91") (pin "1") (pinfunction "1_1") (pintype "passive"))
      (node (ref "C92") (pin "1") (pinfunction "1_1") (pintype "passive"))
      (node (ref "C93") (pin "1") (pinfunction "1_1") (pintype "passive"))
      (node (ref "C94") (pin "1") (pinfunction "1_1") (pintype "passive"))
      (node (ref "C95") (pin "1") (pinfunction "1_1") (pintype "passive"))
      (node (ref "C96") (pin "1") (pinfunction "1_1") (pintype "passive"))
      (node (ref "C97") (pin "1") (pinfunction "1_1") (pintype "passive"))
      (node (ref "C98") (pin "1") (pinfunction "1_1") (pintype "passive"))
      (node (ref "C99") (pin "1") (pinfunction "1_1") (pintype "passive"))
      (node (ref "Q1") (pin "A18") (pinfunction "GND_A18") (pintype "passive"))
      (node (ref "Q1") (pin "A8") (pinfunction "GND_A8") (pintype "passive"))
      (node (ref "Q1") (pin "AA1") (pinfunction "GND_AA1") (pintype "passive"))
      (node (ref "Q1") (pin "AA10") (pinfunction "GND_AA10") (pintype "passive"))
      (node (ref "Q1") (pin "AA18") (pinfunction "GND_AA18") (pintype "passive"))
      (node (ref "Q1") (pin "AA6") (pinfunction "GND_AA6") (pintype "passive"))
      (node (ref "Q1") (pin "AB10") (pinfunction "GND_AB10") (pintype "passive"))
      (node (ref "Q1") (pin "AB15") (pinfunction "GND_AB15") (pintype "passive"))
      (node (ref "Q1") (pin "AB2") (pinfunction "GND_AB2") (pintype "passive"))
      (node (ref "Q1") (pin "AB4") (pinfunction "GND_AB4") (pintype "passive"))
      (node (ref "Q1") (pin "AB8") (pinfunction "GND_AB8") (pintype "passive"))
      (node (ref "Q1") (pin "B15") (pinfunction "GND_B15") (pintype "passive"))
      (node (ref "Q1") (pin "B5") (pinfunction "GND_B5") (pintype "passive"))
      (node (ref "Q1") (pin "C12") (pinfunction "GND_C12") (pintype "passive"))
      (node (ref "Q1") (pin "C2") (pinfunction "GND_C2") (pintype "passive"))
      (node (ref "Q1") (pin "C22") (pinfunction "GND_C22") (pintype "passive"))
      (node (ref "Q1") (pin "D19") (pinfunction "GND_D19") (pintype "passive"))
      (node (ref "Q1") (pin "D9") (pinfunction "GND_D9") (pintype "passive"))
      (node (ref "Q1") (pin "E16") (pinfunction "GND_E16") (pintype "passive"))
      (node (ref "Q1") (pin "E6") (pinfunction "GND_E6") (pintype "passive"))
      (node (ref "Q1") (pin "F13") (pinfunction "GND_F13") (pintype "passive"))
      (node (ref "Q1") (pin "F3") (pinfunction "GND_F3") (pintype "passive"))
      (node (ref "Q1") (pin "G10") (pinfunction "GND_G10") (pintype "passive"))
      (node (ref "Q1") (pin "G12") (pinfunction "RSVDGND_G12") (pintype "passive"))
      (node (ref "Q1") (pin "G14") (pinfunction "VCCBATT_0_G14") (pintype "passive"))
      (node (ref "Q1") (pin "G20") (pinfunction "GND_G20") (pintype "passive"))
      (node (ref "Q1") (pin "H13") (pinfunction "GND_H13") (pintype "passive"))
      (node (ref "Q1") (pin "H15") (pinfunction "GND_H15") (pintype "passive"))
      (node (ref "Q1") (pin "H17") (pinfunction "GND_H17") (pintype "passive"))
      (node (ref "Q1") (pin "H7") (pinfunction "GND_H7") (pintype "passive"))
      (node (ref "Q1") (pin "J10") (pinfunction "GND_J10") (pintype "passive"))
      (node (ref "Q1") (pin "J12") (pinfunction "GND_J12") (pintype "passive"))
      (node (ref "Q1") (pin "J14") (pinfunction "GND_J14") (pintype "passive"))
      (node (ref "Q1") (pin "J4") (pinfunction "GND_J4") (pintype "passive"))
      (node (ref "Q1") (pin "K1") (pinfunction "GND_K1") (pintype "passive"))
      (node (ref "Q1") (pin "K11") (pinfunction "GNDADC_0_K11") (pintype "passive"))
      (node (ref "Q1") (pin "K13") (pinfunction "GND_K13") (pintype "passive"))
      (node (ref "Q1") (pin "K15") (pinfunction "GND_K15") (pintype "passive"))
      (node (ref "Q1") (pin "K21") (pinfunction "GND_K21") (pintype "passive"))
      (node (ref "Q1") (pin "K9") (pinfunction "GND_K9") (pintype "passive"))
      (node (ref "Q1") (pin "L10") (pinfunction "GND_L10") (pintype "passive"))
      (node (ref "Q1") (pin "L14") (pinfunction "GND_L14") (pintype "passive"))
      (node (ref "Q1") (pin "L18") (pinfunction "GND_L18") (pintype "passive"))
      (node (ref "Q1") (pin "L8") (pinfunction "GND_L8") (pintype "passive"))
      (node (ref "Q1") (pin "M13") (pinfunction "GND_M13") (pintype "passive"))
      (node (ref "Q1") (pin "M15") (pinfunction "GND_M15") (pintype "passive"))
      (node (ref "Q1") (pin "M5") (pinfunction "GND_M5") (pintype "passive"))
      (node (ref "Q1") (pin "M9") (pinfunction "GND_M9") (pintype "passive"))
      (node (ref "Q1") (pin "N10") (pinfunction "GND_N10") (pintype "passive"))
      (node (ref "Q1") (pin "N14") (pinfunction "GND_N14") (pintype "passive"))
      (node (ref "Q1") (pin "N2") (pinfunction "GND_N2") (pintype "passive"))
      (node (ref "Q1") (pin "N22") (pinfunction "GND_N22") (pintype "passive"))
      (node (ref "Q1") (pin "P11") (pinfunction "GND_P11") (pintype "passive"))
      (node (ref "Q1") (pin "P13") (pinfunction "GND_P13") (pintype "passive"))
      (node (ref "Q1") (pin "P15") (pinfunction "GND_P15") (pintype "passive"))
      (node (ref "Q1") (pin "P19") (pinfunction "GND_P19") (pintype "passive"))
      (node (ref "Q1") (pin "P9") (pinfunction "GND_P9") (pintype "passive"))
      (node (ref "Q1") (pin "R10") (pinfunction "GND_R10") (pintype "passive"))
      (node (ref "Q1") (pin "R12") (pinfunction "GND_R12") (pintype "passive"))
      (node (ref "Q1") (pin "R14") (pinfunction "GND_R14") (pintype "passive"))
      (node (ref "Q1") (pin "R16") (pinfunction "GND_R16") (pintype "passive"))
      (node (ref "Q1") (pin "R6") (pinfunction "GND_R6") (pintype "passive"))
      (node (ref "Q1") (pin "T13") (pinfunction "GND_T13") (pintype "passive"))
      (node (ref "Q1") (pin "T3") (pinfunction "GND_T3") (pintype "passive"))
      (node (ref "Q1") (pin "T4") (pinfunction "GND_T4") (pintype "passive"))
      (node (ref "Q1") (pin "T5") (pinfunction "GND_T5") (pintype "passive"))
      (node (ref "Q1") (pin "T6") (pinfunction "GND_T6") (pintype "passive"))
      (node (ref "Q1") (pin "T7") (pinfunction "GND_T7") (pintype "passive"))
      (node (ref "Q1") (pin "U10") (pinfunction "GND_U10") (pintype "passive"))
      (node (ref "Q1") (pin "U20") (pinfunction "GND_U20") (pintype "passive"))
      (node (ref "Q1") (pin "U3") (pinfunction "GND_U3") (pintype "passive"))
      (node (ref "Q1") (pin "V1") (pinfunction "GND_V1") (pintype "passive"))
      (node (ref "Q1") (pin "V17") (pinfunction "GND_V17") (pintype "passive"))
      (node (ref "Q1") (pin "V2") (pinfunction "GND_V2") (pintype "passive"))
      (node (ref "Q1") (pin "V3") (pinfunction "GND_V3") (pintype "passive"))
      (node (ref "Q1") (pin "V4") (pinfunction "GND_V4") (pintype "passive"))
      (node (ref "Q1") (pin "V6") (pinfunction "GND_V6") (pintype "passive"))
      (node (ref "Q1") (pin "V8") (pinfunction "GND_V8") (pintype "passive"))
      (node (ref "Q1") (pin "W1") (pinfunction "GND_W1") (pintype "passive"))
      (node (ref "Q1") (pin "W10") (pinfunction "GND_W10") (pintype "passive"))
      (node (ref "Q1") (pin "W14") (pinfunction "GND_W14") (pintype "passive"))
      (node (ref "Q1") (pin "W7") (pinfunction "GND_W7") (pintype "passive"))
      (node (ref "Q1") (pin "Y1") (pinfunction "GND_Y1") (pintype "passive"))
      (node (ref "Q1") (pin "Y10") (pinfunction "GND_Y10") (pintype "passive"))
      (node (ref "Q1") (pin "Y11") (pinfunction "GND_Y11") (pintype "passive"))
      (node (ref "Q1") (pin "Y21") (pinfunction "GND_Y21") (pintype "passive"))
      (node (ref "Q1") (pin "Y3") (pinfunction "GND_Y3") (pintype "passive"))
      (node (ref "Q1") (pin "Y5") (pinfunction "GND_Y5") (pintype "passive"))
      (node (ref "Q1") (pin "Y9") (pinfunction "GND_Y9") (pintype "passive"))
      (node (ref "Q2") (pin "A9") (pinfunction "VSS_A9") (pintype "passive"))
      (node (ref "Q2") (pin "B1") (pinfunction "VSSQ_B1") (pintype "passive"))
      (node (ref "Q2") (pin "B3") (pinfunction "VSS_B3") (pintype "passive"))
      (node (ref "Q2") (pin "B9") (pinfunction "VSSQ_B9") (pintype "passive"))
      (node (ref "Q2") (pin "D1") (pinfunction "VSSQ_D1") (pintype "passive"))
      (node (ref "Q2") (pin "D8") (pinfunction "VSSQ_D8") (pintype "passive"))
      (node (ref "Q2") (pin "E1") (pinfunction "VSS_E1") (pintype "passive"))
      (node (ref "Q2") (pin "E2") (pinfunction "VSSQ_E2") (pintype "passive"))
      (node (ref "Q2") (pin "E8") (pinfunction "VSSQ_E8") (pintype "passive"))
      (node (ref "Q2") (pin "F9") (pinfunction "VSSQ_F9") (pintype "passive"))
      (node (ref "Q2") (pin "G1") (pinfunction "VSSQ_G1") (pintype "passive"))
      (node (ref "Q2") (pin "G8") (pinfunction "VSS_G8") (pintype "passive"))
      (node (ref "Q2") (pin "G9") (pinfunction "VSSQ_G9") (pintype "passive"))
      (node (ref "Q2") (pin "J2") (pinfunction "VSS_J2") (pintype "passive"))
      (node (ref "Q2") (pin "J8") (pinfunction "VSS_J8") (pintype "passive"))
      (node (ref "Q2") (pin "M1") (pinfunction "VSS_M1") (pintype "passive"))
      (node (ref "Q2") (pin "M9") (pinfunction "VSS_M9") (pintype "passive"))
      (node (ref "Q2") (pin "P1") (pinfunction "VSS_P1") (pintype "passive"))
      (node (ref "Q2") (pin "P9") (pinfunction "VSS_P9") (pintype "passive"))
      (node (ref "Q2") (pin "T1") (pinfunction "VSS_T1") (pintype "passive"))
      (node (ref "Q2") (pin "T9") (pinfunction "VSS_T9") (pintype "passive"))
      (node (ref "Q3") (pin "A9") (pinfunction "VSS_A9") (pintype "passive"))
      (node (ref "Q3") (pin "B1") (pinfunction "VSSQ_B1") (pintype "passive"))
      (node (ref "Q3") (pin "B3") (pinfunction "VSS_B3") (pintype "passive"))
      (node (ref "Q3") (pin "B9") (pinfunction "VSSQ_B9") (pintype "passive"))
      (node (ref "Q3") (pin "D1") (pinfunction "VSSQ_D1") (pintype "passive"))
      (node (ref "Q3") (pin "D8") (pinfunction "VSSQ_D8") (pintype "passive"))
      (node (ref "Q3") (pin "E1") (pinfunction "VSS_E1") (pintype "passive"))
      (node (ref "Q3") (pin "E2") (pinfunction "VSSQ_E2") (pintype "passive"))
      (node (ref "Q3") (pin "E8") (pinfunction "VSSQ_E8") (pintype "passive"))
      (node (ref "Q3") (pin "F9") (pinfunction "VSSQ_F9") (pintype "passive"))
      (node (ref "Q3") (pin "G1") (pinfunction "VSSQ_G1") (pintype "passive"))
      (node (ref "Q3") (pin "G8") (pinfunction "VSS_G8") (pintype "passive"))
      (node (ref "Q3") (pin "G9") (pinfunction "VSSQ_G9") (pintype "passive"))
      (node (ref "Q3") (pin "J2") (pinfunction "VSS_J2") (pintype "passive"))
      (node (ref "Q3") (pin "J8") (pinfunction "VSS_J8") (pintype "passive"))
      (node (ref "Q3") (pin "M1") (pinfunction "VSS_M1") (pintype "passive"))
      (node (ref "Q3") (pin "M9") (pinfunction "VSS_M9") (pintype "passive"))
      (node (ref "Q3") (pin "P1") (pinfunction "VSS_P1") (pintype "passive"))
      (node (ref "Q3") (pin "P9") (pinfunction "VSS_P9") (pintype "passive"))
      (node (ref "Q3") (pin "T1") (pinfunction "VSS_T1") (pintype "passive"))
      (node (ref "Q3") (pin "T9") (pinfunction "VSS_T9") (pintype "passive"))
      (node (ref "R1") (pin "1") (pinfunction "1_1") (pintype "passive"))
      (node (ref "R109") (pin "1") (pinfunction "1_1") (pintype "passive"))
      (node (ref "R6") (pin "1") (pinfunction "1_1") (pintype "passive"))
    )
    (net (code "13") (name "VCCPLL") (class "Default")
      (node (ref "C105") (pin "2") (pinfunction "2_2") (pintype "passive"))
      (node (ref "C124") (pin "2") (pinfunction "2_2") (pintype "passive"))
      (node (ref "L1") (pin "2") (pinfunction "2_2") (pintype "passive"))
      (node (ref "Q1") (pin "G13") (pinfunction "VCCPLL_G13") (pintype "passive"))
    )
  )
)
